# 01-main.net
KiCad netlist of a schematic drawn in EAGLE
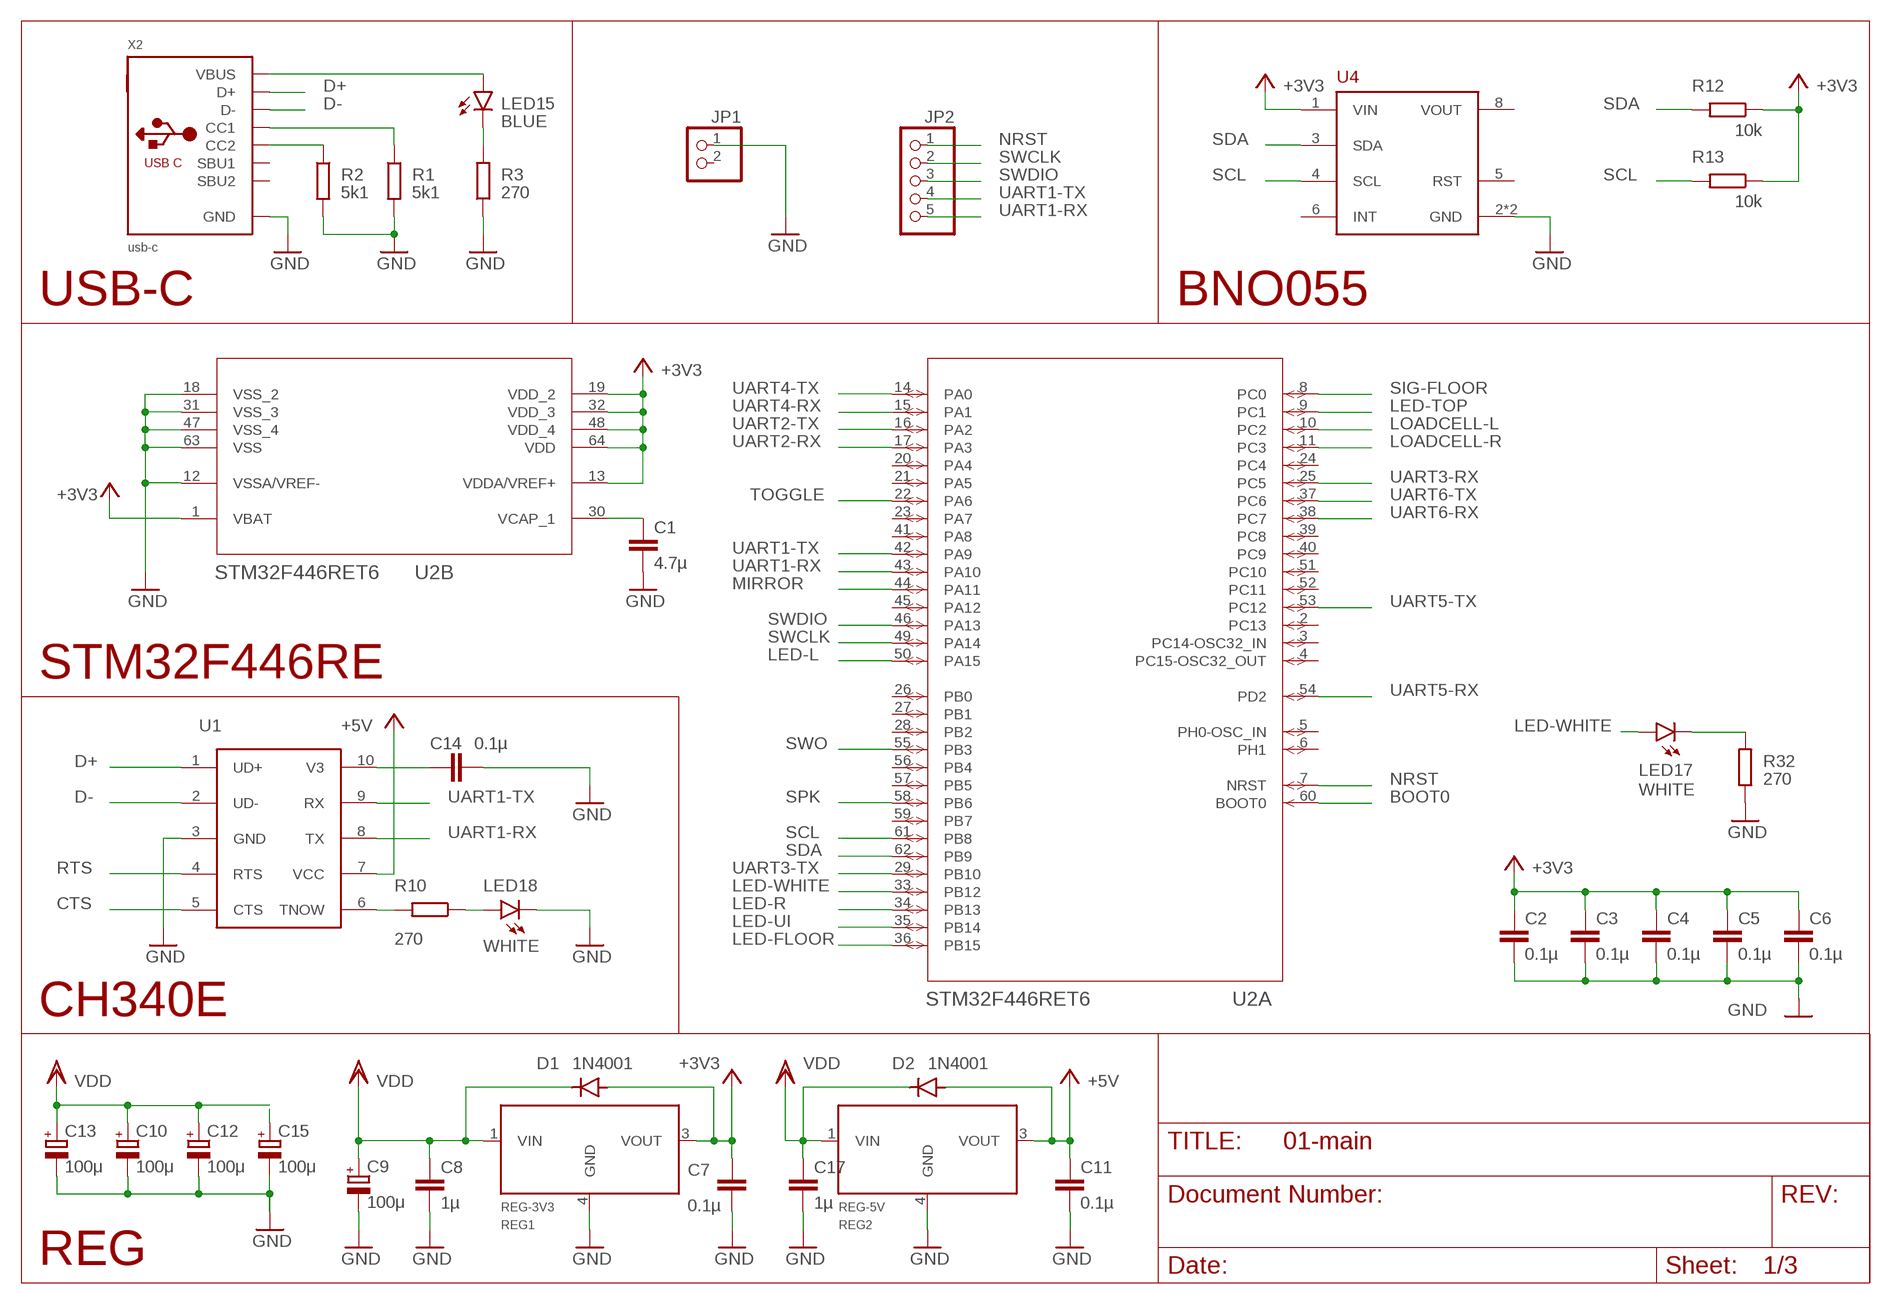
[diagram p0: schematic, sheet 1]
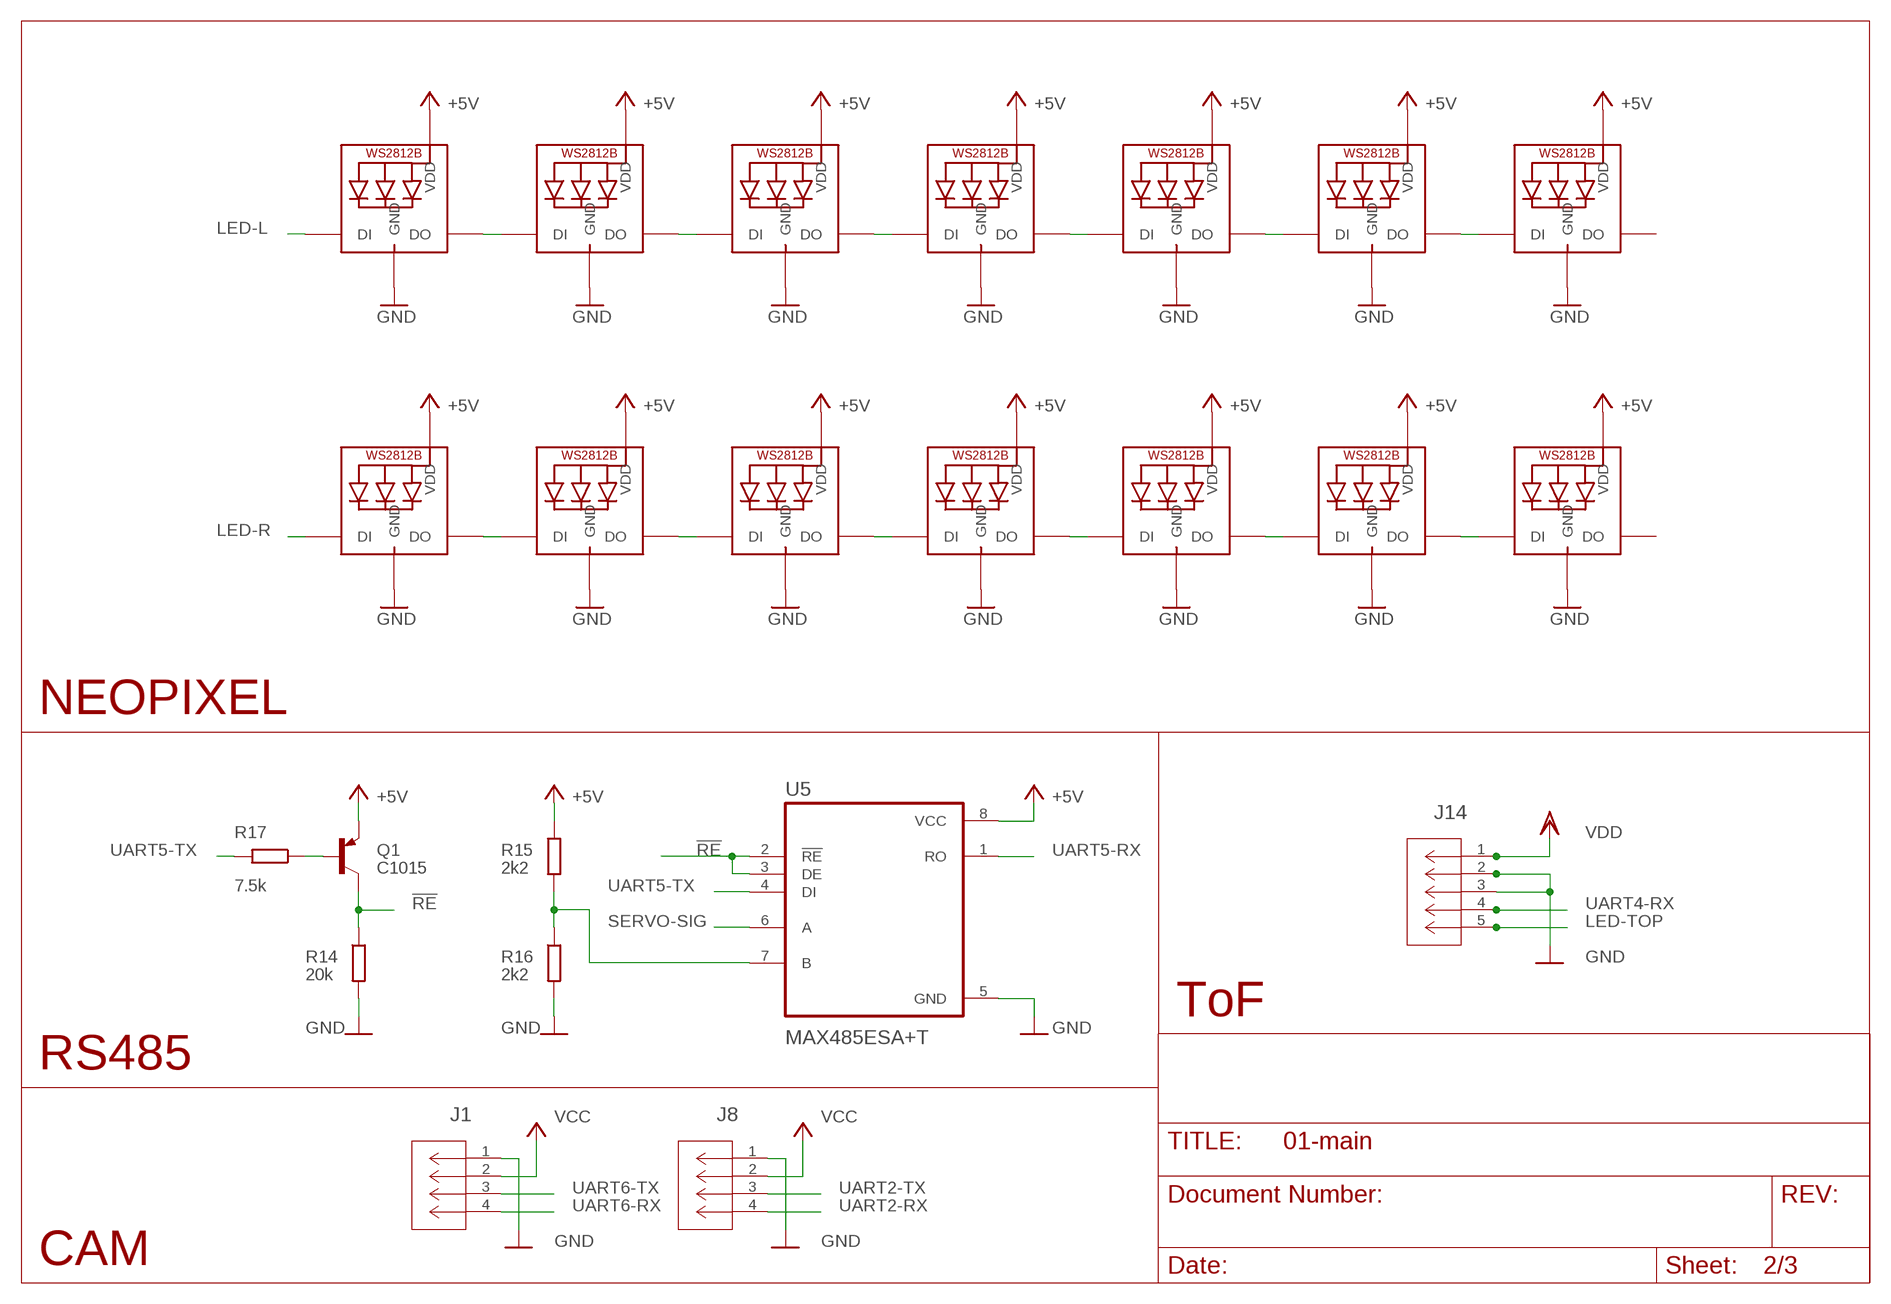
[diagram p1: schematic, sheet 2]
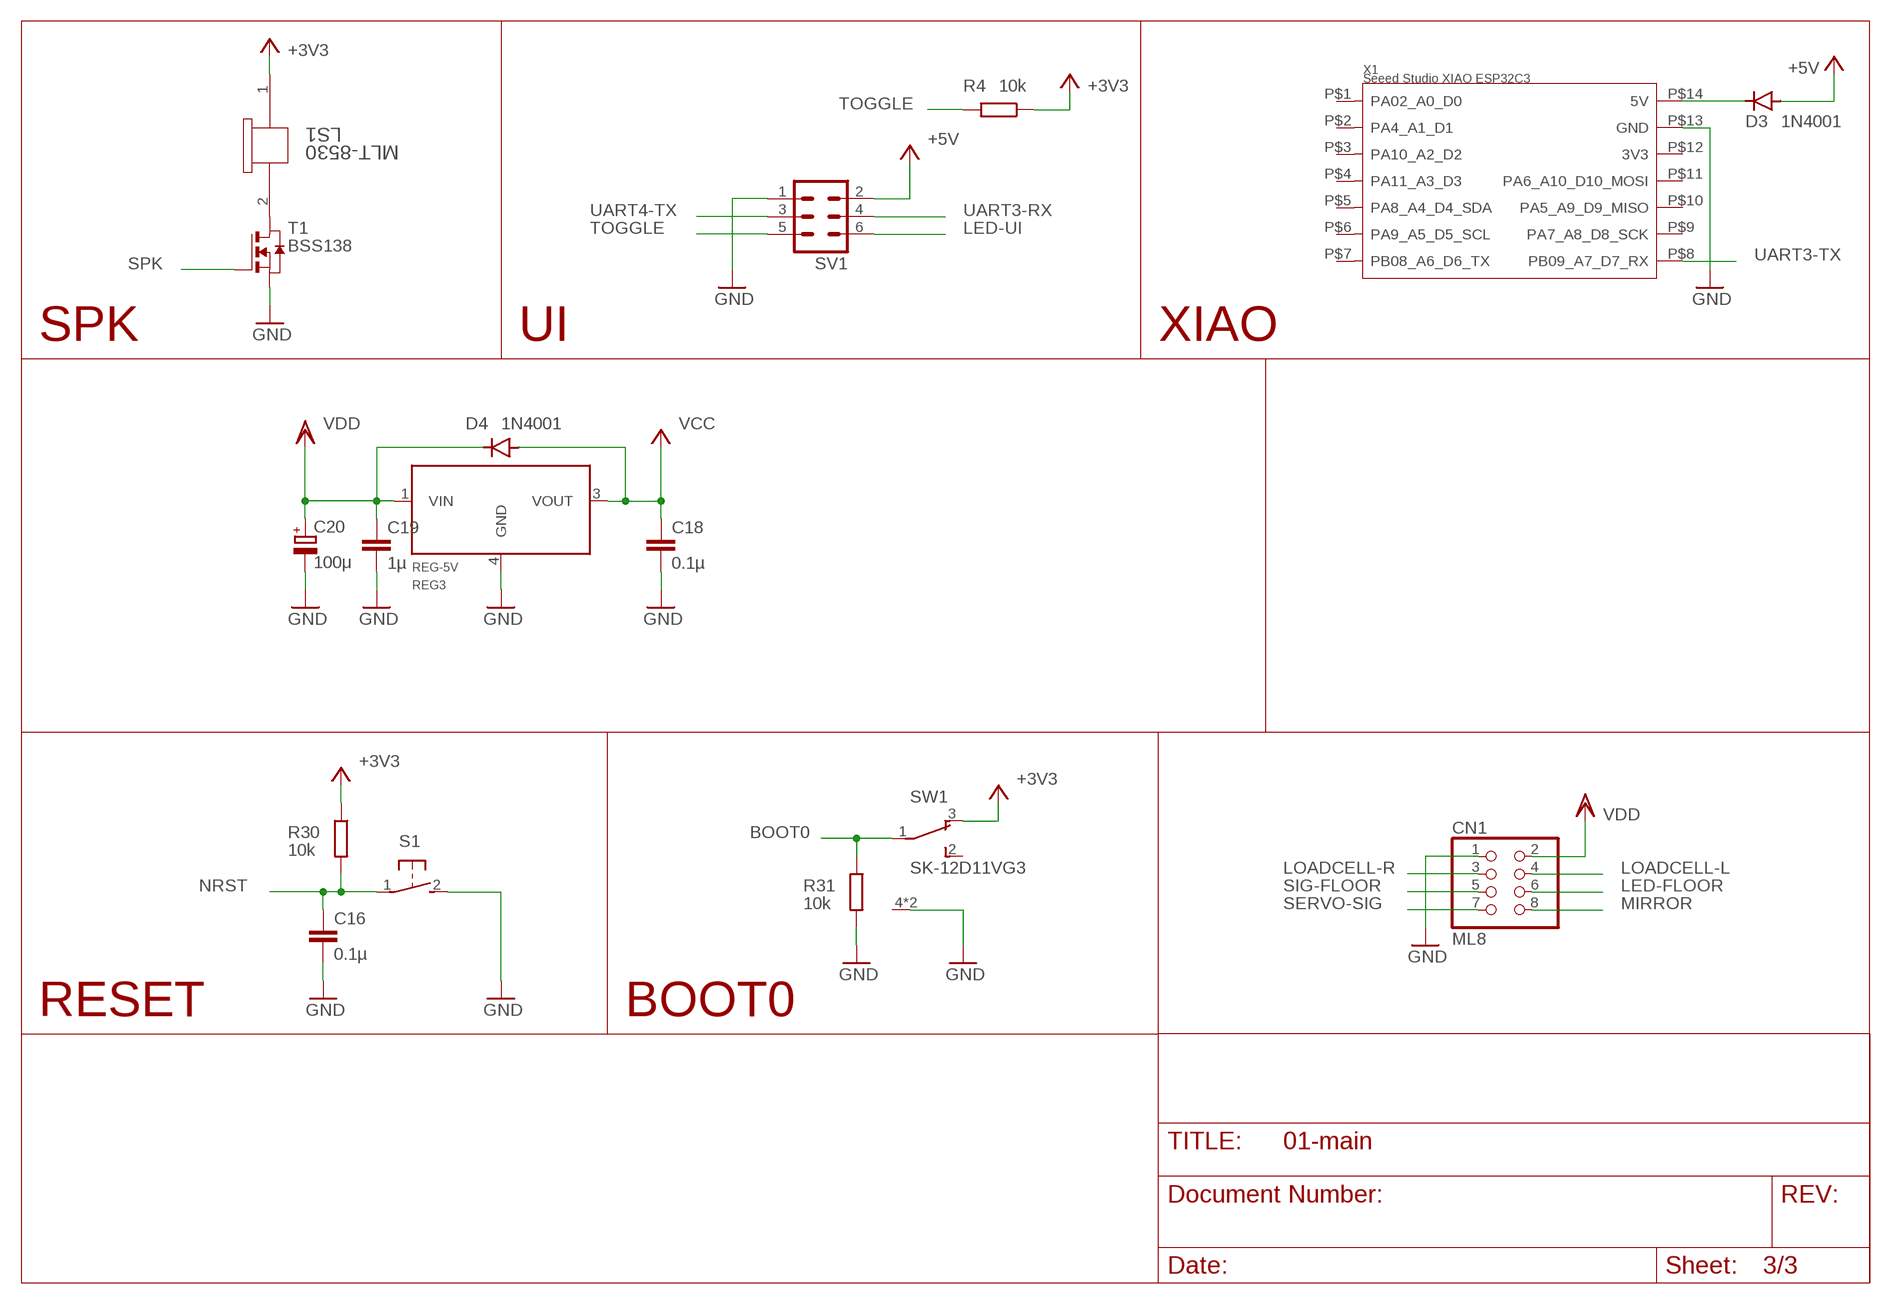
[diagram p2: schematic, sheet 3]

(export (version "E")
  (design (tool "Eeschema 10.0.6"))
  (components
    (comp (ref "C16")
      (value "0.1µ")
      (footprint "eagle-import:C0603")
      (libsource (lib "eagle-import") (part "C-EUC0603"))
    )
    (comp (ref "C18")
      (value "0.1µ")
      (footprint "eagle-import:C0603")
      (libsource (lib "eagle-import") (part "C-EUC0603"))
    )
    (comp (ref "C19")
      (value "1µ")
      (footprint "eagle-import:C0603")
      (libsource (lib "eagle-import") (part "C-EUC0603"))
    )
    (comp (ref "C20")
      (value "100μ")
      (footprint "eagle-import:153CLV-0505")
      (libsource (lib "eagle-import") (part "CPOL-EU153CLV-0505"))
    )
    (comp (ref "CN1")
      (value "ML8")
      (footprint "eagle-import:ML6L")
      (libsource (lib "eagle-import") (part "ML8"))
    )
    (comp (ref "D3")
      (value "1N4001")
      (footprint "eagle-import:SMA-DO214AC")
      (libsource (lib "eagle-import") (part "GF1"))
    )
    (comp (ref "D4")
      (value "1N4001")
      (footprint "eagle-import:SMA-DO214AC")
      (libsource (lib "eagle-import") (part "GF1"))
    )
    (comp (ref "LS1")
      (value "MLT-8530")
      (footprint "eagle-import:MLT-8530_JHE")
      (fields (field (name "COPYRIGHT") "Copyright (C) 2022 Ultra Librarian. All rights reserved."))
      (libsource (lib "eagle-import") (part "MLT-8530"))
    )
    (comp (ref "R4")
      (value "10k")
      (footprint "eagle-import:R0402")
      (libsource (lib "eagle-import") (part "R-EU_R0402"))
    )
    (comp (ref "R30")
      (value "10k")
      (footprint "eagle-import:R0402")
      (libsource (lib "eagle-import") (part "R-EU_R0402"))
    )
    (comp (ref "R31")
      (value "10k")
      (footprint "eagle-import:R0402")
      (libsource (lib "eagle-import") (part "R-EU_R0402"))
    )
    (comp (ref "REG3")
      (value "REG-5V")
      (footprint "eagle-import:MYPARTS_D-PAK_TO252AA")
      (libsource (lib "eagle-import") (part "MYPARTS_NJM7800S-REGULATOR"))
    )
    (comp (ref "S1")
      (value "31-XX")
      (footprint "eagle-import:B3F-31XX")
      (fields (field (name "MPN") "B3F-3100"))
      (libsource (lib "eagle-import") (part "31-XX"))
    )
    (comp (ref "SV1")
      (value "ML6L")
      (footprint "eagle-import:ML6L")
      (libsource (lib "eagle-import") (part "ML6L"))
    )
    (comp (ref "SW1")
      (value "SK-12D11VG3")
      (footprint "eagle-import:SK-12D11VG3")
      (libsource (lib "eagle-import") (part "SK-12D11VG3"))
    )
    (comp (ref "T1")
      (value "BSS138")
      (footprint "eagle-import:SOT-23")
      (libsource (lib "eagle-import") (part "NMOSSOT23"))
    )
    (comp (ref "X1")
      (value "Seeed Studio XIAO ESP32C3")
      (footprint "eagle-import:XIAO-PINHEAD")
      (libsource (lib "eagle-import") (part "SEEEDUINO-XIAO-DIP"))
    )
    (comp (ref "J1")
      (value "22057045")
      (footprint "eagle-import:CON_22057045_MOL")
      (fields (field (name "COPYRIGHT") "Copyright (C) 2022 Ultra Librarian. All rights reserved."))
      (libsource (lib "eagle-import") (part "22057045"))
    )
    (comp (ref "J8")
      (value "22057045")
      (footprint "eagle-import:CON_22057045_MOL")
      (fields (field (name "COPYRIGHT") "Copyright (C) 2022 Ultra Librarian. All rights reserved."))
      (libsource (lib "eagle-import") (part "22057045"))
    )
    (comp (ref "J14")
      (value "22057055")
      (footprint "eagle-import:CON_22057055_MOL")
      (fields (field (name "COPYRIGHT") "Copyright (C) 2022 Ultra Librarian. All rights reserved."))
      (libsource (lib "eagle-import") (part "22057055"))
    )
    (comp (ref "LED1")
      (value "WS2812B_2020")
      (footprint "eagle-import:WS2812B_2020")
      (libsource (lib "eagle-import") (part "WS2812B_2020"))
    )
    (comp (ref "LED2")
      (value "WS2812B_2020")
      (footprint "eagle-import:WS2812B_2020")
      (libsource (lib "eagle-import") (part "WS2812B_2020"))
    )
    (comp (ref "LED3")
      (value "WS2812B_2020")
      (footprint "eagle-import:WS2812B_2020")
      (libsource (lib "eagle-import") (part "WS2812B_2020"))
    )
    (comp (ref "LED4")
      (value "WS2812B_2020")
      (footprint "eagle-import:WS2812B_2020")
      (libsource (lib "eagle-import") (part "WS2812B_2020"))
    )
    (comp (ref "LED5")
      (value "WS2812B_2020")
      (footprint "eagle-import:WS2812B_2020")
      (libsource (lib "eagle-import") (part "WS2812B_2020"))
    )
    (comp (ref "LED6")
      (value "WS2812B_2020")
      (footprint "eagle-import:WS2812B_2020")
      (libsource (lib "eagle-import") (part "WS2812B_2020"))
    )
    (comp (ref "LED7")
      (value "WS2812B_2020")
      (footprint "eagle-import:WS2812B_2020")
      (libsource (lib "eagle-import") (part "WS2812B_2020"))
    )
    (comp (ref "LED8")
      (value "WS2812B_2020")
      (footprint "eagle-import:WS2812B_2020")
      (libsource (lib "eagle-import") (part "WS2812B_2020"))
    )
    (comp (ref "LED9")
      (value "WS2812B_2020")
      (footprint "eagle-import:WS2812B_2020")
      (libsource (lib "eagle-import") (part "WS2812B_2020"))
    )
    (comp (ref "LED10")
      (value "WS2812B_2020")
      (footprint "eagle-import:WS2812B_2020")
      (libsource (lib "eagle-import") (part "WS2812B_2020"))
    )
    (comp (ref "LED11")
      (value "WS2812B_2020")
      (footprint "eagle-import:WS2812B_2020")
      (libsource (lib "eagle-import") (part "WS2812B_2020"))
    )
    (comp (ref "LED12")
      (value "WS2812B_2020")
      (footprint "eagle-import:WS2812B_2020")
      (libsource (lib "eagle-import") (part "WS2812B_2020"))
    )
    (comp (ref "LED13")
      (value "WS2812B_2020")
      (footprint "eagle-import:WS2812B_2020")
      (libsource (lib "eagle-import") (part "WS2812B_2020"))
    )
    (comp (ref "LED14")
      (value "WS2812B_2020")
      (footprint "eagle-import:WS2812B_2020")
      (libsource (lib "eagle-import") (part "WS2812B_2020"))
    )
    (comp (ref "Q1")
      (value "C1015")
      (footprint "eagle-import:SOT23")
      (libsource (lib "eagle-import") (part "BCX71SMD"))
    )
    (comp (ref "R14")
      (value "20k")
      (footprint "eagle-import:R0402")
      (libsource (lib "eagle-import") (part "R-EU_R0402"))
    )
    (comp (ref "R15")
      (value "2k2")
      (footprint "eagle-import:R0402")
      (libsource (lib "eagle-import") (part "R-EU_R0402"))
    )
    (comp (ref "R16")
      (value "2k2")
      (footprint "eagle-import:R0402")
      (libsource (lib "eagle-import") (part "R-EU_R0402"))
    )
    (comp (ref "R17")
      (value "7.5k")
      (footprint "eagle-import:R0402")
      (libsource (lib "eagle-import") (part "R-EU_R0402"))
    )
    (comp (ref "U5")
      (value "MAX485ESA+T")
      (footprint "eagle-import:SOIC127P600X175-8N")
      (fields (field (name "MF") "Maxim Integrated") (field (name "MP") "MAX485ESA"))
      (libsource (lib "eagle-import") (part "MAX485ESA+T"))
    )
    (comp (ref "C1")
      (value "4.7µ")
      (footprint "eagle-import:C0603")
      (libsource (lib "eagle-import") (part "C-EUC0603"))
    )
    (comp (ref "C2")
      (value "0.1µ")
      (footprint "eagle-import:C0603")
      (libsource (lib "eagle-import") (part "C-EUC0603"))
    )
    (comp (ref "C3")
      (value "0.1µ")
      (footprint "eagle-import:C0603")
      (libsource (lib "eagle-import") (part "C-EUC0603"))
    )
    (comp (ref "C4")
      (value "0.1µ")
      (footprint "eagle-import:C0603")
      (libsource (lib "eagle-import") (part "C-EUC0603"))
    )
    (comp (ref "C5")
      (value "0.1µ")
      (footprint "eagle-import:C0603")
      (libsource (lib "eagle-import") (part "C-EUC0603"))
    )
    (comp (ref "C6")
      (value "0.1µ")
      (footprint "eagle-import:C0603")
      (libsource (lib "eagle-import") (part "C-EUC0603"))
    )
    (comp (ref "C7")
      (value "0.1µ")
      (footprint "eagle-import:C0603")
      (libsource (lib "eagle-import") (part "C-EUC0603"))
    )
    (comp (ref "C8")
      (value "1µ")
      (footprint "eagle-import:C0603")
      (libsource (lib "eagle-import") (part "C-EUC0603"))
    )
    (comp (ref "C9")
      (value "100μ")
      (footprint "eagle-import:153CLV-0505")
      (libsource (lib "eagle-import") (part "CPOL-EU153CLV-0505"))
    )
    (comp (ref "C10")
      (value "100μ")
      (footprint "eagle-import:153CLV-0505")
      (libsource (lib "eagle-import") (part "CPOL-EU153CLV-0505"))
    )
    (comp (ref "C11")
      (value "0.1µ")
      (footprint "eagle-import:C0603")
      (libsource (lib "eagle-import") (part "C-EUC0603"))
    )
    (comp (ref "C12")
      (value "100μ")
      (footprint "eagle-import:153CLV-0505")
      (libsource (lib "eagle-import") (part "CPOL-EU153CLV-0505"))
    )
    (comp (ref "C13")
      (value "100μ")
      (footprint "eagle-import:153CLV-0505")
      (libsource (lib "eagle-import") (part "CPOL-EU153CLV-0505"))
    )
    (comp (ref "C14")
      (value "0.1µ")
      (footprint "eagle-import:C0603")
      (libsource (lib "eagle-import") (part "C-EUC0603"))
    )
    (comp (ref "C15")
      (value "100μ")
      (footprint "eagle-import:153CLV-0505")
      (libsource (lib "eagle-import") (part "CPOL-EU153CLV-0505"))
    )
    (comp (ref "C17")
      (value "1µ")
      (footprint "eagle-import:C0603")
      (libsource (lib "eagle-import") (part "C-EUC0603"))
    )
    (comp (ref "D1")
      (value "1N4001")
      (footprint "eagle-import:SMA-DO214AC")
      (libsource (lib "eagle-import") (part "GF1"))
    )
    (comp (ref "D2")
      (value "1N4001")
      (footprint "eagle-import:SMA-DO214AC")
      (libsource (lib "eagle-import") (part "GF1"))
    )
    (comp (ref "JP1")
      (value "PINHD-1X2")
      (footprint "eagle-import:1X02")
      (libsource (lib "eagle-import") (part "PINHD-1X2"))
    )
    (comp (ref "JP2")
      (value "PINHD-1X5")
      (footprint "eagle-import:1X05")
      (libsource (lib "eagle-import") (part "PINHD-1X5"))
    )
    (comp (ref "LED15")
      (value "BLUE")
      (footprint "eagle-import:SML0603")
      (libsource (lib "eagle-import") (part "LEDSML0603"))
    )
    (comp (ref "LED17")
      (value "WHITE")
      (footprint "eagle-import:SML0603")
      (libsource (lib "eagle-import") (part "LEDSML0603"))
    )
    (comp (ref "LED18")
      (value "WHITE")
      (footprint "eagle-import:SML0603")
      (libsource (lib "eagle-import") (part "LEDSML0603"))
    )
    (comp (ref "R1")
      (value "5k1")
      (footprint "eagle-import:R0402")
      (libsource (lib "eagle-import") (part "R-EU_R0402"))
    )
    (comp (ref "R2")
      (value "5k1")
      (footprint "eagle-import:R0402")
      (libsource (lib "eagle-import") (part "R-EU_R0402"))
    )
    (comp (ref "R3")
      (value "270")
      (footprint "eagle-import:R0402")
      (libsource (lib "eagle-import") (part "R-EU_R0402"))
    )
    (comp (ref "R10")
      (value "270")
      (footprint "eagle-import:R0402")
      (libsource (lib "eagle-import") (part "R-EU_R0402"))
    )
    (comp (ref "R12")
      (value "10k")
      (footprint "eagle-import:R0402")
      (libsource (lib "eagle-import") (part "R-EU_R0402"))
    )
    (comp (ref "R13")
      (value "10k")
      (footprint "eagle-import:R0402")
      (libsource (lib "eagle-import") (part "R-EU_R0402"))
    )
    (comp (ref "R32")
      (value "270")
      (footprint "eagle-import:R0402")
      (libsource (lib "eagle-import") (part "R-EU_R0402"))
    )
    (comp (ref "REG1")
      (value "REG-3V3")
      (footprint "eagle-import:MYPARTS_D-PAK_TO252AA")
      (libsource (lib "eagle-import") (part "MYPARTS_NJM7800S-REGULATOR"))
    )
    (comp (ref "REG2")
      (value "REG-5V")
      (footprint "eagle-import:MYPARTS_D-PAK_TO252AA")
      (libsource (lib "eagle-import") (part "MYPARTS_NJM7800S-REGULATOR"))
    )
    (comp (ref "U1")
      (value "CH340ESMD")
      (footprint "eagle-import:MSOP10")
      (libsource (lib "eagle-import") (part "CH340ESMD"))
    )
    (comp (ref "U2")
      (value "STM32F446RET6")
      (footprint "eagle-import:LQFP64-10X10MM")
      (fields (field (name "COPYRIGHT") "Copyright (C) 2022 Ultra Librarian. All rights reserved."))
      (libsource (lib "eagle-import") (part "STM32F446RET6"))
    )
    (comp (ref "U4")
      (value "BNO055")
      (footprint "eagle-import:SOCKET-08")
      (libsource (lib "eagle-import") (part "BNO055"))
    )
    (comp (ref "X2")
      (value "usb-c")
      (footprint "eagle-import:USB_C_CUSB31-CFM2AX-01-X")
      (libsource (lib "eagle-import") (part "USB_C"))
    )
  )
  (nets
    (net (code "1") (name "+3V3") (class "Default")
      (node (ref "C2") (pin "1") (pinfunction "1_1") (pintype "passive"))
      (node (ref "C3") (pin "1") (pinfunction "1_1") (pintype "passive"))
      (node (ref "C4") (pin "1") (pinfunction "1_1") (pintype "passive"))
      (node (ref "C5") (pin "1") (pinfunction "1_1") (pintype "passive"))
      (node (ref "C6") (pin "1") (pinfunction "1_1") (pintype "passive"))
      (node (ref "C7") (pin "1") (pinfunction "1_1") (pintype "passive"))
      (node (ref "D1") (pin "A") (pinfunction "A_A") (pintype "passive"))
      (node (ref "LS1") (pin "1") (pinfunction "1_1") (pintype "passive"))
      (node (ref "R12") (pin "1") (pinfunction "1_1") (pintype "passive"))
      (node (ref "R13") (pin "1") (pinfunction "1_1") (pintype "passive"))
      (node (ref "R30") (pin "1") (pinfunction "1_1") (pintype "passive"))
      (node (ref "R4") (pin "1") (pinfunction "1_1") (pintype "passive"))
      (node (ref "REG1") (pin "3") (pinfunction "VOUT_3") (pintype "passive"))
      (node (ref "SW1") (pin "3") (pinfunction "O_3") (pintype "passive"))
      (node (ref "U2") (pin "1") (pinfunction "VBAT_1") (pintype "power_in"))
      (node (ref "U2") (pin "13") (pinfunction "VDDA/VREF+_13") (pintype "power_in"))
      (node (ref "U2") (pin "19") (pinfunction "VDD_2_19") (pintype "power_in"))
      (node (ref "U2") (pin "32") (pinfunction "VDD_3_32") (pintype "power_in"))
      (node (ref "U2") (pin "48") (pinfunction "VDD_4_48") (pintype "power_in"))
      (node (ref "U2") (pin "64") (pinfunction "VDD_64") (pintype "power_in"))
      (node (ref "U4") (pin "1") (pinfunction "VIN_1") (pintype "power_in"))
    )
    (net (code "2") (name "+5V") (class "Default")
      (node (ref "C11") (pin "1") (pinfunction "1_1") (pintype "passive"))
      (node (ref "D2") (pin "A") (pinfunction "A_A") (pintype "passive"))
      (node (ref "D3") (pin "A") (pinfunction "A_A") (pintype "passive"))
      (node (ref "LED1") (pin "4") (pinfunction "VDD_4") (pintype "power_in"))
      (node (ref "LED10") (pin "4") (pinfunction "VDD_4") (pintype "power_in"))
      (node (ref "LED11") (pin "4") (pinfunction "VDD_4") (pintype "power_in"))
      (node (ref "LED12") (pin "4") (pinfunction "VDD_4") (pintype "power_in"))
      (node (ref "LED13") (pin "4") (pinfunction "VDD_4") (pintype "power_in"))
      (node (ref "LED14") (pin "4") (pinfunction "VDD_4") (pintype "power_in"))
      (node (ref "LED2") (pin "4") (pinfunction "VDD_4") (pintype "power_in"))
      (node (ref "LED3") (pin "4") (pinfunction "VDD_4") (pintype "power_in"))
      (node (ref "LED4") (pin "4") (pinfunction "VDD_4") (pintype "power_in"))
      (node (ref "LED5") (pin "4") (pinfunction "VDD_4") (pintype "power_in"))
      (node (ref "LED6") (pin "4") (pinfunction "VDD_4") (pintype "power_in"))
      (node (ref "LED7") (pin "4") (pinfunction "VDD_4") (pintype "power_in"))
      (node (ref "LED8") (pin "4") (pinfunction "VDD_4") (pintype "power_in"))
      (node (ref "LED9") (pin "4") (pinfunction "VDD_4") (pintype "power_in"))
      (node (ref "Q1") (pin "2") (pinfunction "E_2") (pintype "passive"))
      (node (ref "R15") (pin "1") (pinfunction "1_1") (pintype "passive"))
      (node (ref "REG2") (pin "3") (pinfunction "VOUT_3") (pintype "passive"))
      (node (ref "SV1") (pin "2") (pinfunction "2_2") (pintype "passive"))
      (node (ref "U1") (pin "7") (pinfunction "VCC_7") (pintype "power_in"))
      (node (ref "U5") (pin "8") (pinfunction "VCC_8") (pintype "power_in"))
    )
    (net (code "3") (name "BOOT0") (class "Default")
      (node (ref "R31") (pin "1") (pinfunction "1_1") (pintype "passive"))
      (node (ref "SW1") (pin "1") (pinfunction "P_1") (pintype "passive"))
      (node (ref "U2") (pin "60") (pinfunction "BOOT0_60") (pintype "input"))
    )
    (net (code "4") (name "CTS") (class "Default")
      (node (ref "U1") (pin "5") (pinfunction "CTS_5") (pintype "input"))
    )
    (net (code "5") (name "D+") (class "Default")
      (node (ref "U1") (pin "1") (pinfunction "UD+_1") (pintype "bidirectional"))
      (node (ref "X2") (pin "A6") (pinfunction "D+_A6") (pintype "bidirectional"))
      (node (ref "X2") (pin "B6") (pinfunction "D+_B6") (pintype "bidirectional"))
    )
    (net (code "6") (name "D-") (class "Default")
      (node (ref "U1") (pin "2") (pinfunction "UD-_2") (pintype "bidirectional"))
      (node (ref "X2") (pin "A7") (pinfunction "D-_A7") (pintype "bidirectional"))
      (node (ref "X2") (pin "B7") (pinfunction "D-_B7") (pintype "bidirectional"))
    )
    (net (code "7") (name "GND") (class "Default")
      (node (ref "C1") (pin "2") (pinfunction "2_2") (pintype "passive"))
      (node (ref "C10") (pin "-") (pinfunction "-_-") (pintype "passive"))
      (node (ref "C11") (pin "2") (pinfunction "2_2") (pintype "passive"))
      (node (ref "C12") (pin "-") (pinfunction "-_-") (pintype "passive"))
      (node (ref "C13") (pin "-") (pinfunction "-_-") (pintype "passive"))
      (node (ref "C14") (pin "2") (pinfunction "2_2") (pintype "passive"))
      (node (ref "C15") (pin "-") (pinfunction "-_-") (pintype "passive"))
      (node (ref "C16") (pin "2") (pinfunction "2_2") (pintype "passive"))
      (node (ref "C17") (pin "2") (pinfunction "2_2") (pintype "passive"))
      (node (ref "C18") (pin "2") (pinfunction "2_2") (pintype "passive"))
      (node (ref "C19") (pin "2") (pinfunction "2_2") (pintype "passive"))
      (node (ref "C2") (pin "2") (pinfunction "2_2") (pintype "passive"))
      (node (ref "C20") (pin "-") (pinfunction "-_-") (pintype "passive"))
      (node (ref "C3") (pin "2") (pinfunction "2_2") (pintype "passive"))
      (node (ref "C4") (pin "2") (pinfunction "2_2") (pintype "passive"))
      (node (ref "C5") (pin "2") (pinfunction "2_2") (pintype "passive"))
      (node (ref "C6") (pin "2") (pinfunction "2_2") (pintype "passive"))
      (node (ref "C7") (pin "2") (pinfunction "2_2") (pintype "passive"))
      (node (ref "C8") (pin "2") (pinfunction "2_2") (pintype "passive"))
      (node (ref "C9") (pin "-") (pinfunction "-_-") (pintype "passive"))
      (node (ref "CN1") (pin "1") (pinfunction "1_1") (pintype "passive"))
      (node (ref "J1") (pin "1") (pinfunction "1_1") (pintype "passive"))
      (node (ref "J14") (pin "2") (pinfunction "2_2") (pintype "passive"))
      (node (ref "J14") (pin "3") (pinfunction "3_3") (pintype "passive"))
      (node (ref "J8") (pin "1") (pinfunction "1_1") (pintype "passive"))
      (node (ref "JP1") (pin "1") (pinfunction "1_1") (pintype "passive"))
      (node (ref "LED1") (pin "2") (pinfunction "GND_2") (pintype "power_in"))
      (node (ref "LED10") (pin "2") (pinfunction "GND_2") (pintype "power_in"))
      (node (ref "LED11") (pin "2") (pinfunction "GND_2") (pintype "power_in"))
      (node (ref "LED12") (pin "2") (pinfunction "GND_2") (pintype "power_in"))
      (node (ref "LED13") (pin "2") (pinfunction "GND_2") (pintype "power_in"))
      (node (ref "LED14") (pin "2") (pinfunction "GND_2") (pintype "power_in"))
      (node (ref "LED18") (pin "C") (pinfunction "C_C") (pintype "passive"))
      (node (ref "LED2") (pin "2") (pinfunction "GND_2") (pintype "power_in"))
      (node (ref "LED3") (pin "2") (pinfunction "GND_2") (pintype "power_in"))
      (node (ref "LED4") (pin "2") (pinfunction "GND_2") (pintype "power_in"))
      (node (ref "LED5") (pin "2") (pinfunction "GND_2") (pintype "power_in"))
      (node (ref "LED6") (pin "2") (pinfunction "GND_2") (pintype "power_in"))
      (node (ref "LED7") (pin "2") (pinfunction "GND_2") (pintype "power_in"))
      (node (ref "LED8") (pin "2") (pinfunction "GND_2") (pintype "power_in"))
      (node (ref "LED9") (pin "2") (pinfunction "GND_2") (pintype "power_in"))
      (node (ref "R1") (pin "2") (pinfunction "2_2") (pintype "passive"))
      (node (ref "R14") (pin "2") (pinfunction "2_2") (pintype "passive"))
      (node (ref "R16") (pin "2") (pinfunction "2_2") (pintype "passive"))
      (node (ref "R2") (pin "2") (pinfunction "2_2") (pintype "passive"))
      (node (ref "R3") (pin "1") (pinfunction "1_1") (pintype "passive"))
      (node (ref "R31") (pin "2") (pinfunction "2_2") (pintype "passive"))
      (node (ref "R32") (pin "1") (pinfunction "1_1") (pintype "passive"))
      (node (ref "REG1") (pin "4") (pinfunction "GND_4") (pintype "passive"))
      (node (ref "REG2") (pin "4") (pinfunction "GND_4") (pintype "passive"))
      (node (ref "REG3") (pin "4") (pinfunction "GND_4") (pintype "passive"))
      (node (ref "S1") (pin "2") (pinfunction "S_2") (pintype "passive"))
      (node (ref "SV1") (pin "1") (pinfunction "1_1") (pintype "passive"))
      (node (ref "SW1") (pin "4") (pinfunction "CASE_4") (pintype "bidirectional"))
      (node (ref "SW1") (pin "5") (pinfunction "CASE_5") (pintype "bidirectional"))
      (node (ref "T1") (pin "2") (pinfunction "S_2") (pintype "passive"))
      (node (ref "U1") (pin "3") (pinfunction "GND_3") (pintype "power_in"))
      (node (ref "U2") (pin "12") (pinfunction "VSSA/VREF-_12") (pintype "power_in"))
      (node (ref "U2") (pin "18") (pinfunction "VSS_2_18") (pintype "power_in"))
      (node (ref "U2") (pin "31") (pinfunction "VSS_3_31") (pintype "power_in"))
      (node (ref "U2") (pin "47") (pinfunction "VSS_4_47") (pintype "power_in"))
      (node (ref "U2") (pin "63") (pinfunction "VSS_63") (pintype "power_in"))
      (node (ref "U4") (pin "2") (pinfunction "GND_2") (pintype "power_in"))
      (node (ref "U4") (pin "7") (pinfunction "GND_7") (pintype "power_in"))
      (node (ref "U5") (pin "5") (pinfunction "GND_5") (pintype "power_in"))
      (node (ref "X1") (pin "P$13") (pinfunction "GND_P$13") (pintype "bidirectional"))
      (node (ref "X2") (pin "A1B12") (pinfunction "GND_A1B12") (pintype "power_in"))
      (node (ref "X2") (pin "B1A12") (pinfunction "GND_B1A12") (pintype "power_in"))
    )
    (net (code "8") (name "LED-FLOOR") (class "Default")
      (node (ref "CN1") (pin "6") (pinfunction "6_6") (pintype "passive"))
      (node (ref "U2") (pin "36") (pinfunction "PB15_36") (pintype "bidirectional"))
    )
    (net (code "9") (name "LED-L") (class "Default")
      (node (ref "LED1") (pin "3") (pinfunction "DI_3") (pintype "input"))
      (node (ref "U2") (pin "50") (pinfunction "PA15_50") (pintype "bidirectional"))
    )
    (net (code "10") (name "LED-R") (class "Default")
      (node (ref "LED8") (pin "3") (pinfunction "DI_3") (pintype "input"))
      (node (ref "U2") (pin "34") (pinfunction "PB13_34") (pintype "bidirectional"))
    )
    (net (code "11") (name "LED-TOP") (class "Default")
      (node (ref "J14") (pin "5") (pinfunction "5_5") (pintype "passive"))
      (node (ref "U2") (pin "9") (pinfunction "PC1_9") (pintype "bidirectional"))
    )
    (net (code "12") (name "LED-UI") (class "Default")
      (node (ref "SV1") (pin "6") (pinfunction "6_6") (pintype "passive"))
      (node (ref "U2") (pin "35") (pinfunction "PB14_35") (pintype "bidirectional"))
    )
    (net (code "13") (name "LED-WHITE") (class "Default")
      (node (ref "LED17") (pin "A") (pinfunction "A_A") (pintype "passive"))
      (node (ref "U2") (pin "33") (pinfunction "PB12_33") (pintype "bidirectional"))
    )
    (net (code "14") (name "LOADCELL-L") (class "Default")
      (node (ref "CN1") (pin "4") (pinfunction "4_4") (pintype "passive"))
      (node (ref "U2") (pin "10") (pinfunction "PC2_10") (pintype "bidirectional"))
    )
    (net (code "15") (name "LOADCELL-R") (class "Default")
      (node (ref "CN1") (pin "3") (pinfunction "3_3") (pintype "passive"))
      (node (ref "U2") (pin "11") (pinfunction "PC3_11") (pintype "bidirectional"))
    )
    (net (code "16") (name "MIRROR") (class "Default")
      (node (ref "CN1") (pin "8") (pinfunction "8_8") (pintype "passive"))
      (node (ref "U2") (pin "44") (pinfunction "PA11_44") (pintype "bidirectional"))
    )
    (net (code "17") (name "NRST") (class "Default")
      (node (ref "C16") (pin "1") (pinfunction "1_1") (pintype "passive"))
      (node (ref "JP2") (pin "1") (pinfunction "1_1") (pintype "passive"))
      (node (ref "R30") (pin "2") (pinfunction "2_2") (pintype "passive"))
      (node (ref "S1") (pin "1") (pinfunction "P_1") (pintype "passive"))
      (node (ref "U2") (pin "7") (pinfunction "NRST_7") (pintype "bidirectional"))
    )
    (net (code "18") (name "Net-(D3-C)") (class "Default")
      (node (ref "D3") (pin "K") (pinfunction "C_K") (pintype "passive"))
      (node (ref "X1") (pin "P$14") (pinfunction "5V_P$14") (pintype "bidirectional"))
    )
    (net (code "19") (name "Net-(LED1-DO)") (class "Default")
      (node (ref "LED1") (pin "1") (pinfunction "DO_1") (pintype "output"))
      (node (ref "LED2") (pin "3") (pinfunction "DI_3") (pintype "input"))
    )
    (net (code "20") (name "Net-(LED2-DO)") (class "Default")
      (node (ref "LED2") (pin "1") (pinfunction "DO_1") (pintype "output"))
      (node (ref "LED3") (pin "3") (pinfunction "DI_3") (pintype "input"))
    )
    (net (code "21") (name "Net-(LED3-DO)") (class "Default")
      (node (ref "LED3") (pin "1") (pinfunction "DO_1") (pintype "output"))
      (node (ref "LED4") (pin "3") (pinfunction "DI_3") (pintype "input"))
    )
    (net (code "22") (name "Net-(LED4-DO)") (class "Default")
      (node (ref "LED4") (pin "1") (pinfunction "DO_1") (pintype "output"))
      (node (ref "LED5") (pin "3") (pinfunction "DI_3") (pintype "input"))
    )
    (net (code "23") (name "Net-(LED5-DO)") (class "Default")
      (node (ref "LED5") (pin "1") (pinfunction "DO_1") (pintype "output"))
      (node (ref "LED6") (pin "3") (pinfunction "DI_3") (pintype "input"))
    )
    (net (code "24") (name "Net-(LED6-DO)") (class "Default")
      (node (ref "LED6") (pin "1") (pinfunction "DO_1") (pintype "output"))
      (node (ref "LED7") (pin "3") (pinfunction "DI_3") (pintype "input"))
    )
    (net (code "25") (name "Net-(LED8-DO)") (class "Default")
      (node (ref "LED8") (pin "1") (pinfunction "DO_1") (pintype "output"))
      (node (ref "LED9") (pin "3") (pinfunction "DI_3") (pintype "input"))
    )
    (net (code "26") (name "Net-(LED10-DI)") (class "Default")
      (node (ref "LED10") (pin "3") (pinfunction "DI_3") (pintype "input"))
      (node (ref "LED9") (pin "1") (pinfunction "DO_1") (pintype "output"))
    )
    (net (code "27") (name "Net-(LED10-DO)") (class "Default")
      (node (ref "LED10") (pin "1") (pinfunction "DO_1") (pintype "output"))
      (node (ref "LED11") (pin "3") (pinfunction "DI_3") (pintype "input"))
    )
    (net (code "28") (name "Net-(LED11-DO)") (class "Default")
      (node (ref "LED11") (pin "1") (pinfunction "DO_1") (pintype "output"))
      (node (ref "LED12") (pin "3") (pinfunction "DI_3") (pintype "input"))
    )
    (net (code "29") (name "Net-(LED12-DO)") (class "Default")
      (node (ref "LED12") (pin "1") (pinfunction "DO_1") (pintype "output"))
      (node (ref "LED13") (pin "3") (pinfunction "DI_3") (pintype "input"))
    )
    (net (code "30") (name "Net-(LED13-DO)") (class "Default")
      (node (ref "LED13") (pin "1") (pinfunction "DO_1") (pintype "output"))
      (node (ref "LED14") (pin "3") (pinfunction "DI_3") (pintype "input"))
    )
    (net (code "31") (name "Net-(LED15-PadA)") (class "Default")
      (node (ref "LED15") (pin "A") (pinfunction "A_A") (pintype "passive"))
      (node (ref "X2") (pin "A4B9") (pinfunction "VBUS_A4B9") (pintype "power_in"))
      (node (ref "X2") (pin "B4A9") (pinfunction "VBUS_B4A9") (pintype "power_in"))
    )
    (net (code "32") (name "Net-(LED15-PadC)") (class "Default")
      (node (ref "LED15") (pin "C") (pinfunction "C_C") (pintype "passive"))
      (node (ref "R3") (pin "2") (pinfunction "2_2") (pintype "passive"))
    )
    (net (code "33") (name "Net-(LED17-PadC)") (class "Default")
      (node (ref "LED17") (pin "C") (pinfunction "C_C") (pintype "passive"))
      (node (ref "R32") (pin "2") (pinfunction "2_2") (pintype "passive"))
    )
    (net (code "34") (name "Net-(LED18-PadA)") (class "Default")
      (node (ref "LED18") (pin "A") (pinfunction "A_A") (pintype "passive"))
      (node (ref "R10") (pin "1") (pinfunction "1_1") (pintype "passive"))
    )
    (net (code "35") (name "Net-(Q1-B)") (class "Default")
      (node (ref "Q1") (pin "1") (pinfunction "B_1") (pintype "passive"))
      (node (ref "R17") (pin "1") (pinfunction "1_1") (pintype "passive"))
    )
    (net (code "36") (name "Net-(T1-D)") (class "Default")
      (node (ref "LS1") (pin "2") (pinfunction "2_2") (pintype "passive"))
      (node (ref "T1") (pin "1") (pinfunction "D_1") (pintype "passive"))
    )
    (net (code "37") (name "Net-(U1-TNOW)") (class "Default")
      (node (ref "R10") (pin "2") (pinfunction "2_2") (pintype "passive"))
      (node (ref "U1") (pin "6") (pinfunction "TNOW_6") (pintype "output"))
    )
    (net (code "38") (name "Net-(U1-V3)") (class "Default")
      (node (ref "C14") (pin "1") (pinfunction "1_1") (pintype "passive"))
      (node (ref "U1") (pin "10") (pinfunction "V3_10") (pintype "power_in"))
    )
    (net (code "39") (name "Net-(U2B-VCAP_1)") (class "Default")
      (node (ref "C1") (pin "1") (pinfunction "1_1") (pintype "passive"))
      (node (ref "U2") (pin "30") (pinfunction "VCAP_1_30") (pintype "power_in"))
    )
    (net (code "40") (name "Net-(U5-B)") (class "Default")
      (node (ref "R15") (pin "2") (pinfunction "2_2") (pintype "passive"))
      (node (ref "R16") (pin "1") (pinfunction "1_1") (pintype "passive"))
      (node (ref "U5") (pin "7") (pinfunction "B_7") (pintype "bidirectional"))
    )
    (net (code "41") (name "Net-(X2-CC1)") (class "Default")
      (node (ref "R1") (pin "1") (pinfunction "1_1") (pintype "passive"))
      (node (ref "X2") (pin "A5") (pinfunction "CC1_A5") (pintype "bidirectional"))
    )
    (net (code "42") (name "Net-(X2-CC2)") (class "Default")
      (node (ref "R2") (pin "1") (pinfunction "1_1") (pintype "passive"))
      (node (ref "X2") (pin "B5") (pinfunction "CC2_B5") (pintype "bidirectional"))
    )
    (net (code "43") (name "RTS") (class "Default")
      (node (ref "U1") (pin "4") (pinfunction "RTS_4") (pintype "output"))
    )
    (net (code "44") (name "SCL") (class "Default")
      (node (ref "R13") (pin "2") (pinfunction "2_2") (pintype "passive"))
      (node (ref "U2") (pin "61") (pinfunction "PB8_61") (pintype "bidirectional"))
      (node (ref "U4") (pin "4") (pinfunction "SCL_4") (pintype "bidirectional"))
    )
    (net (code "45") (name "SDA") (class "Default")
      (node (ref "R12") (pin "2") (pinfunction "2_2") (pintype "passive"))
      (node (ref "U2") (pin "62") (pinfunction "PB9_62") (pintype "bidirectional"))
      (node (ref "U4") (pin "3") (pinfunction "SDA_3") (pintype "bidirectional"))
    )
    (net (code "46") (name "SERVO-SIG") (class "Default")
      (node (ref "CN1") (pin "7") (pinfunction "7_7") (pintype "passive"))
      (node (ref "U5") (pin "6") (pinfunction "A_6") (pintype "bidirectional"))
    )
    (net (code "47") (name "SIG-FLOOR") (class "Default")
      (node (ref "CN1") (pin "5") (pinfunction "5_5") (pintype "passive"))
      (node (ref "U2") (pin "8") (pinfunction "PC0_8") (pintype "bidirectional"))
    )
    (net (code "48") (name "SPK") (class "Default")
      (node (ref "T1") (pin "3") (pinfunction "G_3") (pintype "passive"))
      (node (ref "U2") (pin "58") (pinfunction "PB6_58") (pintype "bidirectional"))
    )
    (net (code "49") (name "SWCLK") (class "Default")
      (node (ref "JP2") (pin "2") (pinfunction "2_2") (pintype "passive"))
      (node (ref "U2") (pin "49") (pinfunction "PA14_49") (pintype "bidirectional"))
    )
    (net (code "50") (name "SWDIO") (class "Default")
      (node (ref "JP2") (pin "3") (pinfunction "3_3") (pintype "passive"))
      (node (ref "U2") (pin "46") (pinfunction "PA13_46") (pintype "bidirectional"))
    )
    (net (code "51") (name "SWO") (class "Default")
      (node (ref "U2") (pin "55") (pinfunction "PB3_55") (pintype "bidirectional"))
    )
    (net (code "52") (name "TOGGLE") (class "Default")
      (node (ref "R4") (pin "2") (pinfunction "2_2") (pintype "passive"))
      (node (ref "SV1") (pin "5") (pinfunction "5_5") (pintype "passive"))
      (node (ref "U2") (pin "22") (pinfunction "PA6_22") (pintype "bidirectional"))
    )
    (net (code "53") (name "UART1-RX") (class "Default")
      (node (ref "JP2") (pin "5") (pinfunction "5_5") (pintype "passive"))
      (node (ref "U1") (pin "8") (pinfunction "TX_8") (pintype "output"))
      (node (ref "U2") (pin "43") (pinfunction "PA10_43") (pintype "bidirectional"))
    )
    (net (code "54") (name "UART1-TX") (class "Default")
      (node (ref "JP2") (pin "4") (pinfunction "4_4") (pintype "passive"))
      (node (ref "U1") (pin "9") (pinfunction "RX_9") (pintype "input"))
      (node (ref "U2") (pin "42") (pinfunction "PA9_42") (pintype "bidirectional"))
    )
    (net (code "55") (name "UART2-RX") (class "Default")
      (node (ref "J8") (pin "4") (pinfunction "4_4") (pintype "passive"))
      (node (ref "U2") (pin "17") (pinfunction "PA3_17") (pintype "bidirectional"))
    )
    (net (code "56") (name "UART2-TX") (class "Default")
      (node (ref "J8") (pin "3") (pinfunction "3_3") (pintype "passive"))
      (node (ref "U2") (pin "16") (pinfunction "PA2_16") (pintype "bidirectional"))
    )
    (net (code "57") (name "UART3-RX") (class "Default")
      (node (ref "SV1") (pin "4") (pinfunction "4_4") (pintype "passive"))
      (node (ref "U2") (pin "25") (pinfunction "PC5_25") (pintype "bidirectional"))
    )
    (net (code "58") (name "UART3-TX") (class "Default")
      (node (ref "U2") (pin "29") (pinfunction "PB10_29") (pintype "bidirectional"))
      (node (ref "X1") (pin "P$8") (pinfunction "PB09_A7_D7_RX_P$8") (pintype "bidirectional"))
    )
    (net (code "59") (name "UART4-RX") (class "Default")
      (node (ref "J14") (pin "4") (pinfunction "4_4") (pintype "passive"))
      (node (ref "U2") (pin "15") (pinfunction "PA1_15") (pintype "bidirectional"))
    )
    (net (code "60") (name "UART4-TX") (class "Default")
      (node (ref "SV1") (pin "3") (pinfunction "3_3") (pintype "passive"))
      (node (ref "U2") (pin "14") (pinfunction "PA0_14") (pintype "bidirectional"))
    )
    (net (code "61") (name "UART5-RX") (class "Default")
      (node (ref "U2") (pin "54") (pinfunction "PD2_54") (pintype "bidirectional"))
      (node (ref "U5") (pin "1") (pinfunction "RO_1") (pintype "output"))
    )
    (net (code "62") (name "UART5-TX") (class "Default")
      (node (ref "R17") (pin "2") (pinfunction "2_2") (pintype "passive"))
      (node (ref "U2") (pin "53") (pinfunction "PC12_53") (pintype "bidirectional"))
      (node (ref "U5") (pin "4") (pinfunction "DI_4") (pintype "input"))
    )
    (net (code "63") (name "UART6-RX") (class "Default")
      (node (ref "J1") (pin "4") (pinfunction "4_4") (pintype "passive"))
      (node (ref "U2") (pin "38") (pinfunction "PC7_38") (pintype "bidirectional"))
    )
    (net (code "64") (name "UART6-TX") (class "Default")
      (node (ref "J1") (pin "3") (pinfunction "3_3") (pintype "passive"))
      (node (ref "U2") (pin "37") (pinfunction "PC6_37") (pintype "bidirectional"))
    )
    (net (code "65") (name "VCC") (class "Default")
      (node (ref "C18") (pin "1") (pinfunction "1_1") (pintype "passive"))
      (node (ref "D4") (pin "A") (pinfunction "A_A") (pintype "passive"))
      (node (ref "J1") (pin "2") (pinfunction "2_2") (pintype "passive"))
      (node (ref "J8") (pin "2") (pinfunction "2_2") (pintype "passive"))
      (node (ref "REG3") (pin "3") (pinfunction "VOUT_3") (pintype "passive"))
    )
    (net (code "66") (name "VDD") (class "Default")
      (node (ref "C10") (pin "+") (pinfunction "+_+") (pintype "passive"))
      (node (ref "C12") (pin "+") (pinfunction "+_+") (pintype "passive"))
      (node (ref "C13") (pin "+") (pinfunction "+_+") (pintype "passive"))
      (node (ref "C15") (pin "+") (pinfunction "+_+") (pintype "passive"))
      (node (ref "C17") (pin "1") (pinfunction "1_1") (pintype "passive"))
      (node (ref "C19") (pin "1") (pinfunction "1_1") (pintype "passive"))
      (node (ref "C20") (pin "+") (pinfunction "+_+") (pintype "passive"))
      (node (ref "C8") (pin "1") (pinfunction "1_1") (pintype "passive"))
      (node (ref "C9") (pin "+") (pinfunction "+_+") (pintype "passive"))
      (node (ref "CN1") (pin "2") (pinfunction "2_2") (pintype "passive"))
      (node (ref "D1") (pin "K") (pinfunction "C_K") (pintype "passive"))
      (node (ref "D2") (pin "K") (pinfunction "C_K") (pintype "passive"))
      (node (ref "D4") (pin "K") (pinfunction "C_K") (pintype "passive"))
      (node (ref "J14") (pin "1") (pinfunction "1_1") (pintype "passive"))
      (node (ref "REG1") (pin "1") (pinfunction "VIN_1") (pintype "passive"))
      (node (ref "REG2") (pin "1") (pinfunction "VIN_1") (pintype "passive"))
      (node (ref "REG3") (pin "1") (pinfunction "VIN_1") (pintype "passive"))
    )
    (net (code "67") (name "VOUT") (class "Default")
      (node (ref "U4") (pin "8") (pinfunction "VOUT_8") (pintype "power_in"))
    )
    (net (code "68") (name "unconnected-(JP1-Pad2)") (class "Default")
      (node (ref "JP1") (pin "2") (pinfunction "2_2") (pintype "passive"))
    )
    (net (code "69") (name "unconnected-(LED7-DO-Pad1)") (class "Default")
      (node (ref "LED7") (pin "1") (pinfunction "DO_1") (pintype "output"))
    )
    (net (code "70") (name "unconnected-(LED14-DO-Pad1)") (class "Default")
      (node (ref "LED14") (pin "1") (pinfunction "DO_1") (pintype "output"))
    )
    (net (code "71") (name "unconnected-(SW1-S-Pad2)") (class "Default")
      (node (ref "SW1") (pin "2") (pinfunction "S_2") (pintype "passive"))
    )
    (net (code "72") (name "unconnected-(U2A-PA4-Pad20)") (class "Default")
      (node (ref "U2") (pin "20") (pinfunction "PA4_20") (pintype "bidirectional"))
    )
    (net (code "73") (name "unconnected-(U2A-PA5-Pad21)") (class "Default")
      (node (ref "U2") (pin "21") (pinfunction "PA5_21") (pintype "bidirectional"))
    )
    (net (code "74") (name "unconnected-(U2A-PA7-Pad23)") (class "Default")
      (node (ref "U2") (pin "23") (pinfunction "PA7_23") (pintype "bidirectional"))
    )
    (net (code "75") (name "unconnected-(U2A-PA8-Pad41)") (class "Default")
      (node (ref "U2") (pin "41") (pinfunction "PA8_41") (pintype "bidirectional"))
    )
    (net (code "76") (name "unconnected-(U2A-PA12-Pad45)") (class "Default")
      (node (ref "U2") (pin "45") (pinfunction "PA12_45") (pintype "bidirectional"))
    )
    (net (code "77") (name "unconnected-(U2A-PB0-Pad26)") (class "Default")
      (node (ref "U2") (pin "26") (pinfunction "PB0_26") (pintype "bidirectional"))
    )
    (net (code "78") (name "unconnected-(U2A-PB1-Pad27)") (class "Default")
      (node (ref "U2") (pin "27") (pinfunction "PB1_27") (pintype "bidirectional"))
    )
    (net (code "79") (name "unconnected-(U2A-PB2-Pad28)") (class "Default")
      (node (ref "U2") (pin "28") (pinfunction "PB2_28") (pintype "bidirectional"))
    )
    (net (code "80") (name "unconnected-(U2A-PB4-Pad56)") (class "Default")
      (node (ref "U2") (pin "56") (pinfunction "PB4_56") (pintype "bidirectional"))
    )
    (net (code "81") (name "unconnected-(U2A-PB5-Pad57)") (class "Default")
      (node (ref "U2") (pin "57") (pinfunction "PB5_57") (pintype "bidirectional"))
    )
    (net (code "82") (name "unconnected-(U2A-PB7-Pad59)") (class "Default")
      (node (ref "U2") (pin "59") (pinfunction "PB7_59") (pintype "bidirectional"))
    )
    (net (code "83") (name "unconnected-(U2A-PC4-Pad24)") (class "Default")
      (node (ref "U2") (pin "24") (pinfunction "PC4_24") (pintype "bidirectional"))
    )
    (net (code "84") (name "unconnected-(U2A-PC8-Pad39)") (class "Default")
      (node (ref "U2") (pin "39") (pinfunction "PC8_39") (pintype "bidirectional"))
    )
    (net (code "85") (name "unconnected-(U2A-PC9-Pad40)") (class "Default")
      (node (ref "U2") (pin "40") (pinfunction "PC9_40") (pintype "bidirectional"))
    )
    (net (code "86") (name "unconnected-(U2A-PC10-Pad51)") (class "Default")
      (node (ref "U2") (pin "51") (pinfunction "PC10_51") (pintype "bidirectional"))
    )
    (net (code "87") (name "unconnected-(U2A-PC11-Pad52)") (class "Default")
      (node (ref "U2") (pin "52") (pinfunction "PC11_52") (pintype "bidirectional"))
    )
    (net (code "88") (name "unconnected-(U2A-PC13-Pad2)") (class "Default")
      (node (ref "U2") (pin "2") (pinfunction "PC13_2") (pintype "bidirectional"))
    )
    (net (code "89") (name "unconnected-(U2A-PC14-OSC32_IN-Pad3)") (class "Default")
      (node (ref "U2") (pin "3") (pinfunction "PC14-OSC32_IN_3") (pintype "bidirectional"))
    )
    (net (code "90") (name "unconnected-(U2A-PC15-OSC32_OUT-Pad4)") (class "Default")
      (node (ref "U2") (pin "4") (pinfunction "PC15-OSC32_OUT_4") (pintype "bidirectional"))
    )
    (net (code "91") (name "unconnected-(U2A-PH0-OSC_IN-Pad5)") (class "Default")
      (node (ref "U2") (pin "5") (pinfunction "PH0-OSC_IN_5") (pintype "bidirectional"))
    )
    (net (code "92") (name "unconnected-(U2A-PH1-Pad6)") (class "Default")
      (node (ref "U2") (pin "6") (pinfunction "PH1_6") (pintype "bidirectional"))
    )
    (net (code "93") (name "unconnected-(U4-INT-Pad6)") (class "Default")
      (node (ref "U4") (pin "6") (pinfunction "INT_6") (pintype "bidirectional"))
    )
    (net (code "94") (name "unconnected-(U4-RST-Pad5)") (class "Default")
      (node (ref "U4") (pin "5") (pinfunction "RST_5") (pintype "bidirectional"))
    )
    (net (code "95") (name "unconnected-(X1-3V3-PadP$12)") (class "Default")
      (node (ref "X1") (pin "P$12") (pinfunction "3V3_P$12") (pintype "bidirectional"))
    )
    (net (code "96") (name "unconnected-(X1-PA02_A0_D0-PadP$1)") (class "Default")
      (node (ref "X1") (pin "P$1") (pinfunction "PA02_A0_D0_P$1") (pintype "bidirectional"))
    )
    (net (code "97") (name "unconnected-(X1-PA4_A1_D1-PadP$2)") (class "Default")
      (node (ref "X1") (pin "P$2") (pinfunction "PA4_A1_D1_P$2") (pintype "bidirectional"))
    )
    (net (code "98") (name "unconnected-(X1-PA5_A9_D9_MISO-PadP$10)") (class "Default")
      (node (ref "X1") (pin "P$10") (pinfunction "PA5_A9_D9_MISO_P$10") (pintype "bidirectional"))
    )
    (net (code "99") (name "unconnected-(X1-PA6_A10_D10_MOSI-PadP$11)") (class "Default")
      (node (ref "X1") (pin "P$11") (pinfunction "PA6_A10_D10_MOSI_P$11") (pintype "bidirectional"))
    )
    (net (code "100") (name "unconnected-(X1-PA7_A8_D8_SCK-PadP$9)") (class "Default")
      (node (ref "X1") (pin "P$9") (pinfunction "PA7_A8_D8_SCK_P$9") (pintype "bidirectional"))
    )
    (net (code "101") (name "unconnected-(X1-PA8_A4_D4_SDA-PadP$5)") (class "Default")
      (node (ref "X1") (pin "P$5") (pinfunction "PA8_A4_D4_SDA_P$5") (pintype "bidirectional"))
    )
    (net (code "102") (name "unconnected-(X1-PA9_A5_D5_SCL-PadP$6)") (class "Default")
      (node (ref "X1") (pin "P$6") (pinfunction "PA9_A5_D5_SCL_P$6") (pintype "bidirectional"))
    )
    (net (code "103") (name "unconnected-(X1-PA10_A2_D2-PadP$3)") (class "Default")
      (node (ref "X1") (pin "P$3") (pinfunction "PA10_A2_D2_P$3") (pintype "bidirectional"))
    )
    (net (code "104") (name "unconnected-(X1-PA11_A3_D3-PadP$4)") (class "Default")
      (node (ref "X1") (pin "P$4") (pinfunction "PA11_A3_D3_P$4") (pintype "bidirectional"))
    )
    (net (code "105") (name "unconnected-(X1-PB08_A6_D6_TX-PadP$7)") (class "Default")
      (node (ref "X1") (pin "P$7") (pinfunction "PB08_A6_D6_TX_P$7") (pintype "bidirectional"))
    )
    (net (code "106") (name "unconnected-(X2-SBU1-PadA8)") (class "Default")
      (node (ref "X2") (pin "A8") (pinfunction "SBU1_A8") (pintype "bidirectional"))
    )
    (net (code "107") (name "unconnected-(X2-SBU2-PadB8)") (class "Default")
      (node (ref "X2") (pin "B8") (pinfunction "SBU2_B8") (pintype "bidirectional"))
    )
    (net (code "108") (name "~{RE}") (class "Default")
      (node (ref "Q1") (pin "3") (pinfunction "C_3") (pintype "passive"))
      (node (ref "R14") (pin "1") (pinfunction "1_1") (pintype "passive"))
      (node (ref "U5") (pin "2") (pinfunction "~{RE}_2") (pintype "input"))
      (node (ref "U5") (pin "3") (pinfunction "DE_3") (pintype "input"))
    )
  )
)
